# timer_rtc_io.net
KiCad netlist of a schematic drawn in EAGLE
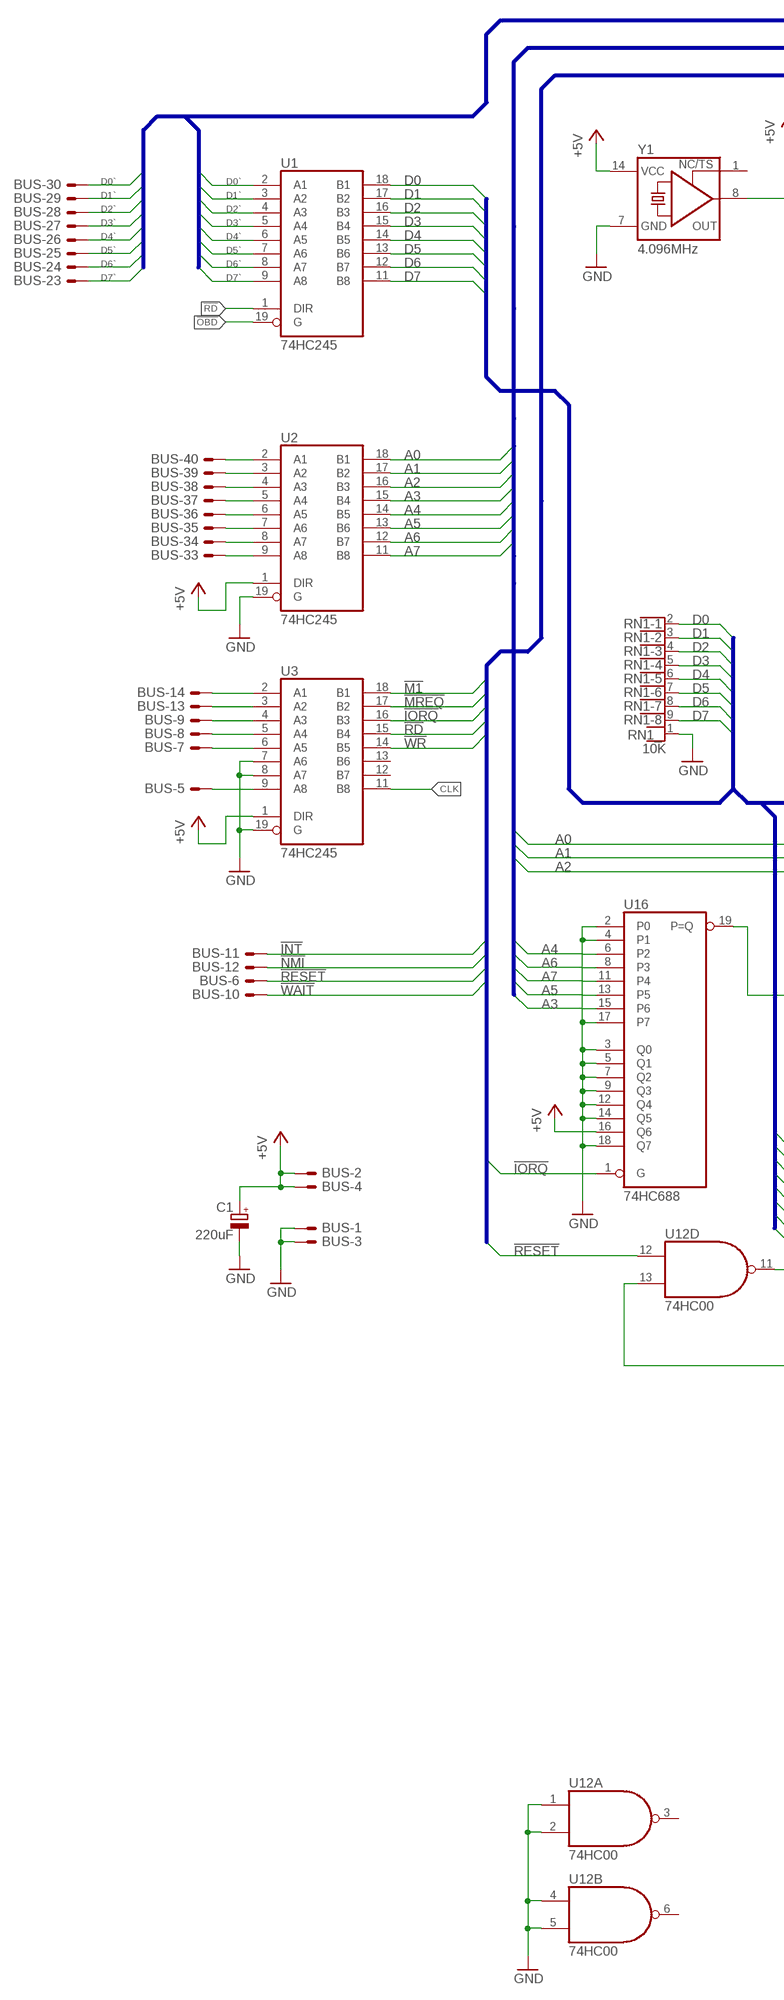
[diagram p0: schematic, sheet 1, part 1 of 2]
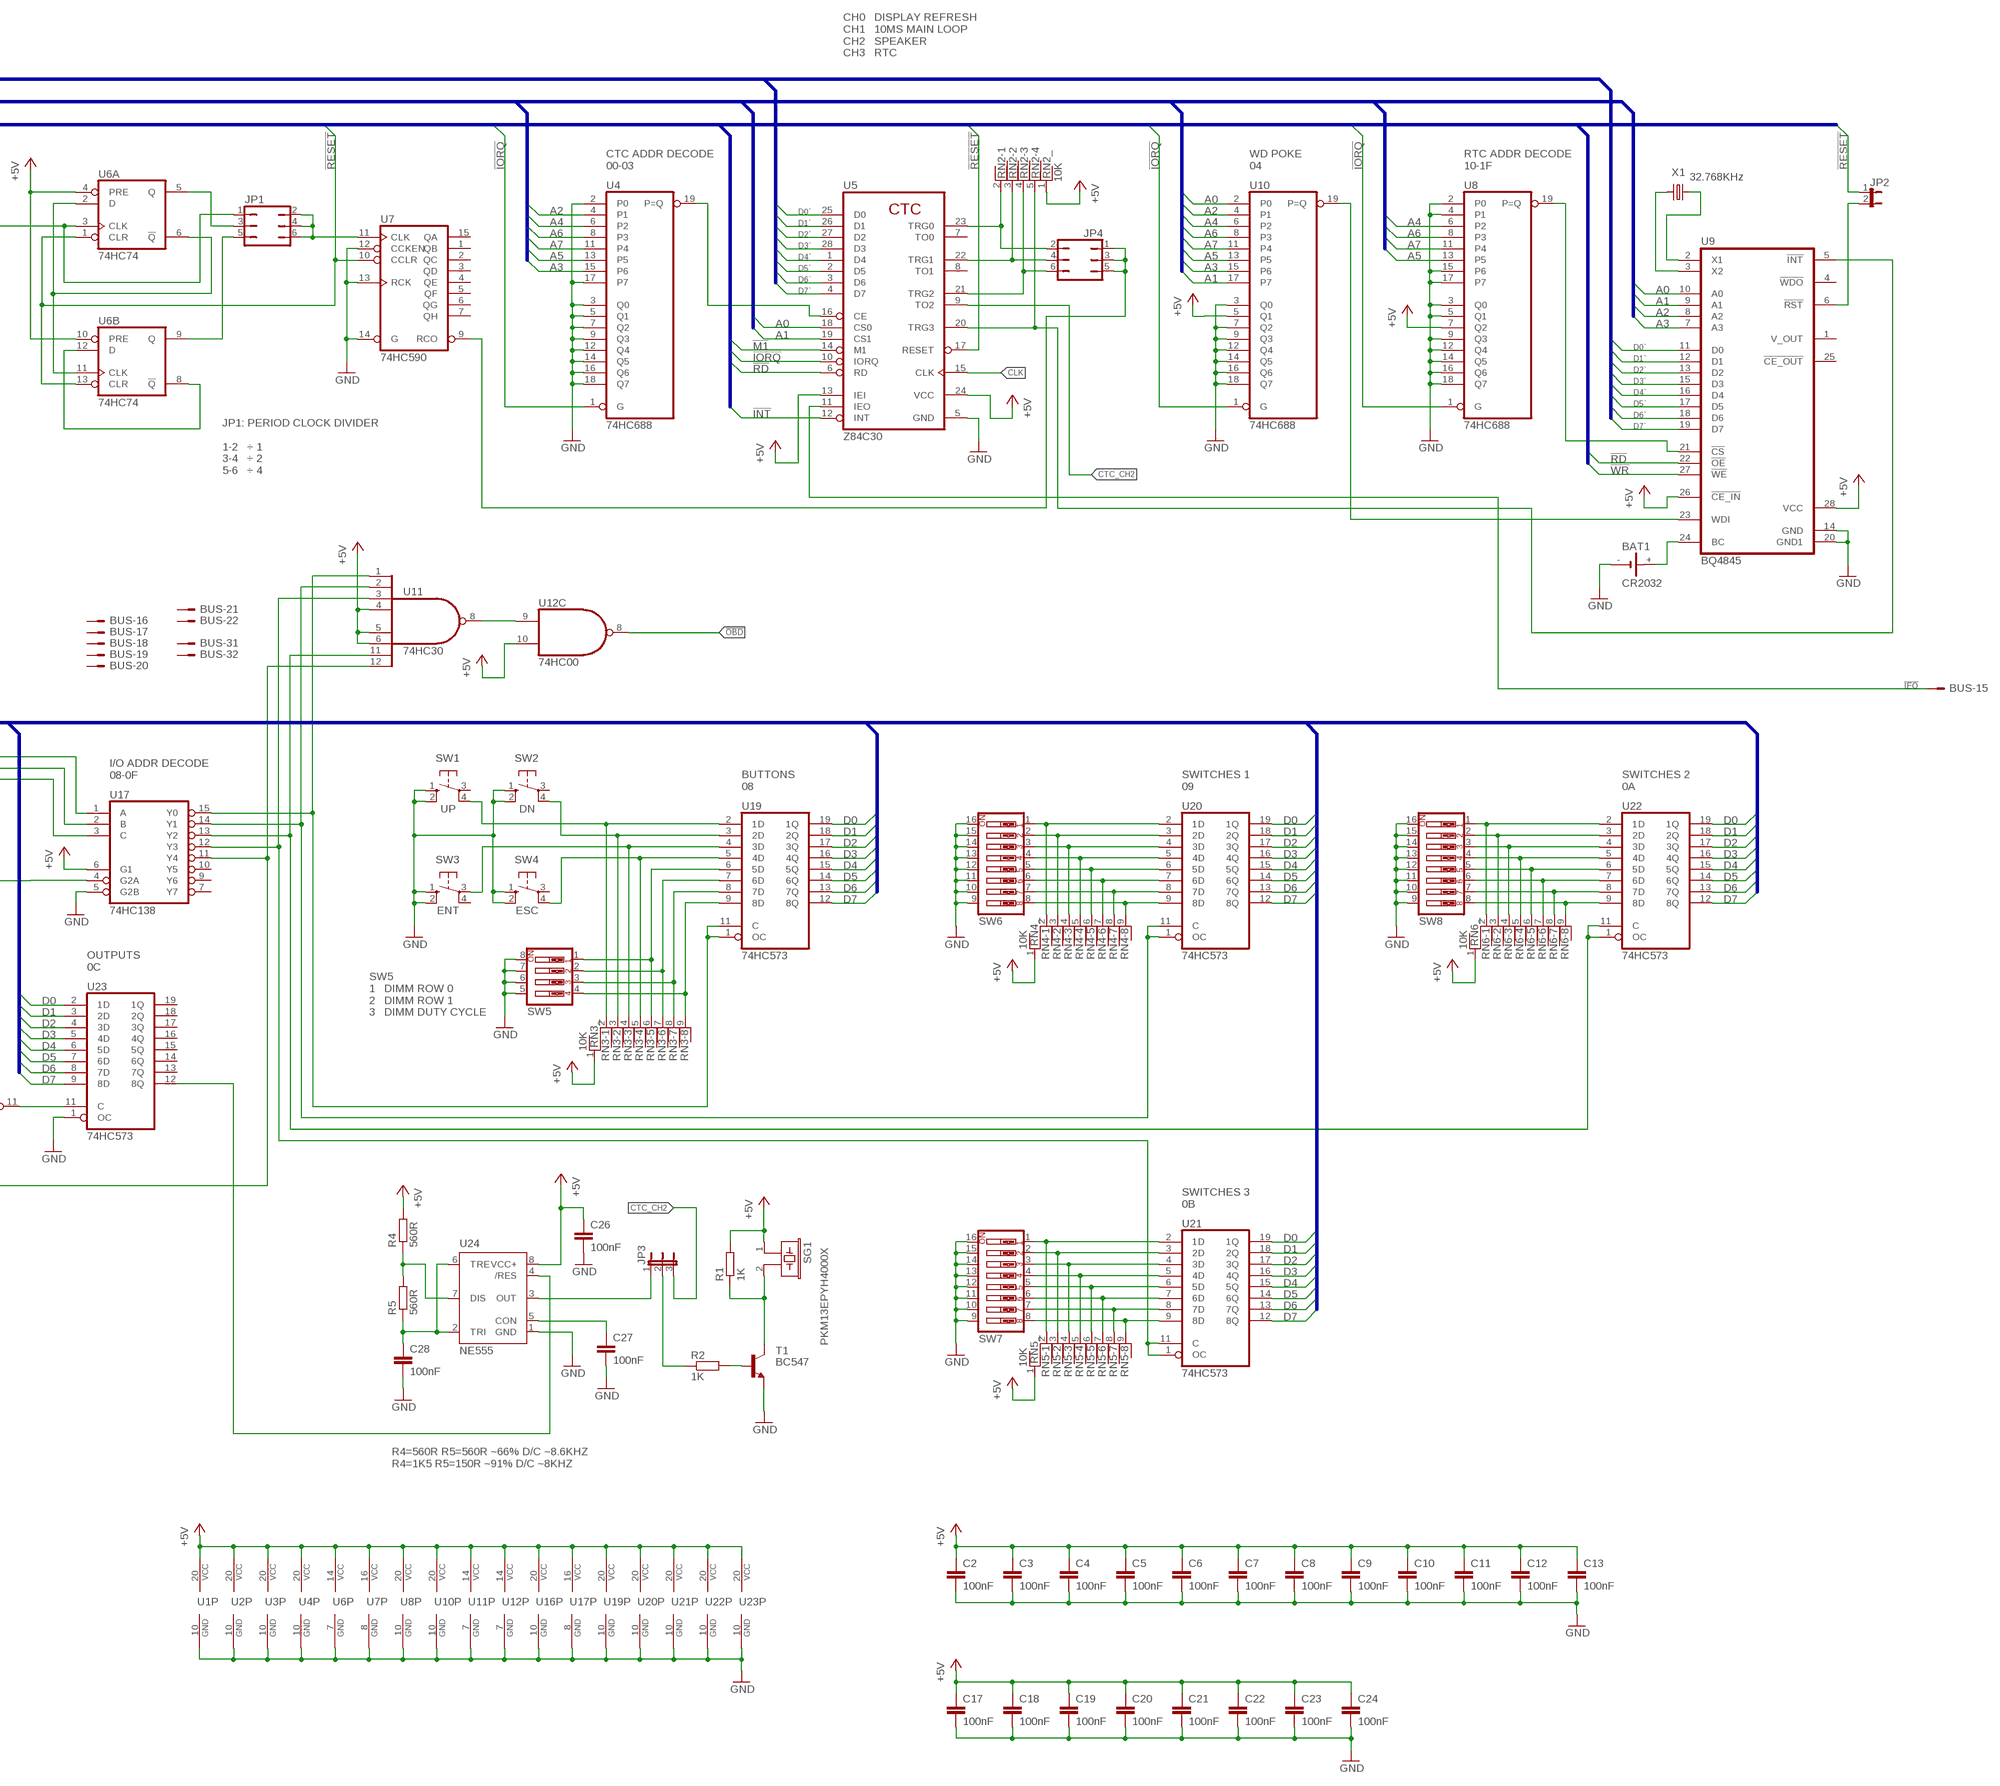
[diagram p1: schematic, sheet 1, part 2 of 2]

(export (version "E")
  (design (tool "Eeschema 10.0.6"))
  (components
    (comp (ref "BAT1")
      (value "CR2032")
      (footprint "eagle-import:CR2032-SMD")
      (libsource (lib "eagle-import") (part "CR2032-SMD"))
    )
    (comp (ref "BUS")
      (value "HDR40")
      (footprint "eagle-import:HDR40")
      (libsource (lib "eagle-import") (part "HDR40"))
    )
    (comp (ref "C1")
      (value "220uF")
      (footprint "eagle-import:E3,5-8")
      (libsource (lib "eagle-import") (part "CPOL-EUE3.5-8"))
    )
    (comp (ref "C2")
      (value "100nF")
      (footprint "eagle-import:C050-025X075")
      (libsource (lib "eagle-import") (part "C-EU050-025X075"))
    )
    (comp (ref "C3")
      (value "100nF")
      (footprint "eagle-import:C050-025X075")
      (libsource (lib "eagle-import") (part "C-EU050-025X075"))
    )
    (comp (ref "C4")
      (value "100nF")
      (footprint "eagle-import:C050-025X075")
      (libsource (lib "eagle-import") (part "C-EU050-025X075"))
    )
    (comp (ref "C5")
      (value "100nF")
      (footprint "eagle-import:C050-025X075")
      (libsource (lib "eagle-import") (part "C-EU050-025X075"))
    )
    (comp (ref "C6")
      (value "100nF")
      (footprint "eagle-import:C050-025X075")
      (libsource (lib "eagle-import") (part "C-EU050-025X075"))
    )
    (comp (ref "C7")
      (value "100nF")
      (footprint "eagle-import:C050-025X075")
      (libsource (lib "eagle-import") (part "C-EU050-025X075"))
    )
    (comp (ref "C8")
      (value "100nF")
      (footprint "eagle-import:C050-025X075")
      (libsource (lib "eagle-import") (part "C-EU050-025X075"))
    )
    (comp (ref "C9")
      (value "100nF")
      (footprint "eagle-import:C050-025X075")
      (libsource (lib "eagle-import") (part "C-EU050-025X075"))
    )
    (comp (ref "C10")
      (value "100nF")
      (footprint "eagle-import:C050-025X075")
      (libsource (lib "eagle-import") (part "C-EU050-025X075"))
    )
    (comp (ref "C11")
      (value "100nF")
      (footprint "eagle-import:C050-025X075")
      (libsource (lib "eagle-import") (part "C-EU050-025X075"))
    )
    (comp (ref "C12")
      (value "100nF")
      (footprint "eagle-import:C050-025X075")
      (libsource (lib "eagle-import") (part "C-EU050-025X075"))
    )
    (comp (ref "C13")
      (value "100nF")
      (footprint "eagle-import:C050-025X075")
      (libsource (lib "eagle-import") (part "C-EU050-025X075"))
    )
    (comp (ref "C17")
      (value "100nF")
      (footprint "eagle-import:C050-025X075")
      (libsource (lib "eagle-import") (part "C-EU050-025X075"))
    )
    (comp (ref "C18")
      (value "100nF")
      (footprint "eagle-import:C050-025X075")
      (libsource (lib "eagle-import") (part "C-EU050-025X075"))
    )
    (comp (ref "C19")
      (value "100nF")
      (footprint "eagle-import:C050-025X075")
      (libsource (lib "eagle-import") (part "C-EU050-025X075"))
    )
    (comp (ref "C20")
      (value "100nF")
      (footprint "eagle-import:C050-025X075")
      (libsource (lib "eagle-import") (part "C-EU050-025X075"))
    )
    (comp (ref "C21")
      (value "100nF")
      (footprint "eagle-import:C050-025X075")
      (libsource (lib "eagle-import") (part "C-EU050-025X075"))
    )
    (comp (ref "C22")
      (value "100nF")
      (footprint "eagle-import:C050-025X075")
      (libsource (lib "eagle-import") (part "C-EU050-025X075"))
    )
    (comp (ref "C23")
      (value "100nF")
      (footprint "eagle-import:C050-025X075")
      (libsource (lib "eagle-import") (part "C-EU050-025X075"))
    )
    (comp (ref "C24")
      (value "100nF")
      (footprint "eagle-import:C050-025X075")
      (libsource (lib "eagle-import") (part "C-EU050-025X075"))
    )
    (comp (ref "C26")
      (value "100nF")
      (footprint "eagle-import:C050-025X075")
      (libsource (lib "eagle-import") (part "C-EU050-025X075"))
    )
    (comp (ref "C27")
      (value "100nF")
      (footprint "eagle-import:C050-025X075")
      (libsource (lib "eagle-import") (part "C-EU050-025X075"))
    )
    (comp (ref "C28")
      (value "100nF")
      (footprint "eagle-import:C050-025X075")
      (libsource (lib "eagle-import") (part "C-EU050-025X075"))
    )
    (comp (ref "JP1")
      (value "JP3Q")
      (footprint "eagle-import:JP3Q")
      (libsource (lib "eagle-import") (part "JP3Q"))
    )
    (comp (ref "JP2")
      (value "JP1E")
      (footprint "eagle-import:JP1")
      (libsource (lib "eagle-import") (part "JP1E"))
    )
    (comp (ref "JP3")
      (value "JP2E")
      (footprint "eagle-import:JP2")
      (libsource (lib "eagle-import") (part "JP2E"))
    )
    (comp (ref "JP4")
      (value "JP3Q")
      (footprint "eagle-import:JP3Q")
      (libsource (lib "eagle-import") (part "JP3Q"))
    )
    (comp (ref "R1")
      (value "1K")
      (footprint "eagle-import:0207_10")
      (libsource (lib "eagle-import") (part "R-EU_0207/10"))
    )
    (comp (ref "R2")
      (value "1K")
      (footprint "eagle-import:0207_10")
      (libsource (lib "eagle-import") (part "R-EU_0207/10"))
    )
    (comp (ref "R4")
      (value "560R")
      (footprint "eagle-import:0207_10")
      (libsource (lib "eagle-import") (part "R-EU_0207/10"))
    )
    (comp (ref "R5")
      (value "560R")
      (footprint "eagle-import:0207_10")
      (libsource (lib "eagle-import") (part "R-EU_0207/10"))
    )
    (comp (ref "RN1")
      (value "10K")
      (footprint "eagle-import:RN-9")
      (libsource (lib "eagle-import") (part "RNX8"))
    )
    (comp (ref "RN2")
      (value "10K")
      (footprint "eagle-import:RN-5")
      (libsource (lib "eagle-import") (part "RNX4"))
    )
    (comp (ref "RN3")
      (value "10K")
      (footprint "eagle-import:RN-9")
      (libsource (lib "eagle-import") (part "RNX8"))
    )
    (comp (ref "RN4")
      (value "10K")
      (footprint "eagle-import:RN-9")
      (libsource (lib "eagle-import") (part "RNX8"))
    )
    (comp (ref "RN5")
      (value "10K")
      (footprint "eagle-import:RN-9")
      (libsource (lib "eagle-import") (part "RNX8"))
    )
    (comp (ref "RN6")
      (value "10K")
      (footprint "eagle-import:RN-9")
      (libsource (lib "eagle-import") (part "RNX8"))
    )
    (comp (ref "SG1")
      (value "PKM13EPYH4000X")
      (footprint "eagle-import:PKM13EPYH400X")
      (libsource (lib "eagle-import") (part "PKM13EPYH4000X"))
    )
    (comp (ref "SW1")
      (value "10-XX")
      (footprint "eagle-import:B3F-10XX")
      (fields (field (name "MPN") "B3F-1000"))
      (libsource (lib "eagle-import") (part "10-XX"))
    )
    (comp (ref "SW2")
      (value "10-XX")
      (footprint "eagle-import:B3F-10XX")
      (fields (field (name "MPN") "B3F-1000"))
      (libsource (lib "eagle-import") (part "10-XX"))
    )
    (comp (ref "SW3")
      (value "10-XX")
      (footprint "eagle-import:B3F-10XX")
      (fields (field (name "MPN") "B3F-1000"))
      (libsource (lib "eagle-import") (part "10-XX"))
    )
    (comp (ref "SW4")
      (value "10-XX")
      (footprint "eagle-import:B3F-10XX")
      (fields (field (name "MPN") "B3F-1000"))
      (libsource (lib "eagle-import") (part "10-XX"))
    )
    (comp (ref "SW5")
      (value "SW_DIP-4")
      (footprint "eagle-import:EDG-04")
      (libsource (lib "eagle-import") (part "SW_DIP-4"))
    )
    (comp (ref "SW6")
      (value "SW_DIP-8")
      (footprint "eagle-import:EDG-08")
      (libsource (lib "eagle-import") (part "SW_DIP-8"))
    )
    (comp (ref "SW7")
      (value "SW_DIP-8")
      (footprint "eagle-import:EDG-08")
      (libsource (lib "eagle-import") (part "SW_DIP-8"))
    )
    (comp (ref "SW8")
      (value "SW_DIP-8")
      (footprint "eagle-import:EDG-08")
      (libsource (lib "eagle-import") (part "SW_DIP-8"))
    )
    (comp (ref "T1")
      (value "BC547")
      (footprint "eagle-import:TO92")
      (libsource (lib "eagle-import") (part "BC547"))
    )
    (comp (ref "U1")
      (value "74HC245")
      (footprint "eagle-import:DIL20")
      (libsource (lib "eagle-import") (part "74245NLS"))
    )
    (comp (ref "U2")
      (value "74HC245")
      (footprint "eagle-import:DIL20")
      (libsource (lib "eagle-import") (part "74245NLS"))
    )
    (comp (ref "U3")
      (value "74HC245")
      (footprint "eagle-import:DIL20")
      (libsource (lib "eagle-import") (part "74245NLS"))
    )
    (comp (ref "U4")
      (value "74HC688")
      (footprint "eagle-import:DIL20")
      (libsource (lib "eagle-import") (part "74688NLS"))
    )
    (comp (ref "U5")
      (value "Z84C30")
      (footprint "eagle-import:DIL28")
      (libsource (lib "eagle-import") (part "Z80CTC"))
    )
    (comp (ref "U6")
      (value "74HC74")
      (footprint "eagle-import:DIL14")
      (libsource (lib "eagle-import") (part "7474NLS"))
    )
    (comp (ref "U7")
      (value "74HC590")
      (footprint "eagle-import:DIL16")
      (libsource (lib "eagle-import") (part "74590NLS"))
    )
    (comp (ref "U8")
      (value "74HC688")
      (footprint "eagle-import:DIL20")
      (libsource (lib "eagle-import") (part "74688NLS"))
    )
    (comp (ref "U9")
      (value "BQ4845")
      (footprint "eagle-import:DIL28-6")
      (libsource (lib "eagle-import") (part "BQ4845P"))
    )
    (comp (ref "U10")
      (value "74HC688")
      (footprint "eagle-import:DIL20")
      (libsource (lib "eagle-import") (part "74688NLS"))
    )
    (comp (ref "U11")
      (value "74HC30")
      (footprint "eagle-import:DIL14")
      (libsource (lib "eagle-import") (part "7430NLS"))
    )
    (comp (ref "U12")
      (value "74HC00")
      (footprint "eagle-import:DIL14")
      (libsource (lib "eagle-import") (part "7400NLS"))
    )
    (comp (ref "U16")
      (value "74HC688")
      (footprint "eagle-import:DIL20")
      (libsource (lib "eagle-import") (part "74688NLS"))
    )
    (comp (ref "U17")
      (value "74HC138")
      (footprint "eagle-import:DIL16")
      (libsource (lib "eagle-import") (part "74138NLS"))
    )
    (comp (ref "U19")
      (value "74HC573")
      (footprint "eagle-import:DIL20")
      (libsource (lib "eagle-import") (part "74573NHC"))
    )
    (comp (ref "U20")
      (value "74HC573")
      (footprint "eagle-import:DIL20")
      (libsource (lib "eagle-import") (part "74573NHC"))
    )
    (comp (ref "U21")
      (value "74HC573")
      (footprint "eagle-import:DIL20")
      (libsource (lib "eagle-import") (part "74573NHC"))
    )
    (comp (ref "U22")
      (value "74HC573")
      (footprint "eagle-import:DIL20")
      (libsource (lib "eagle-import") (part "74573NHC"))
    )
    (comp (ref "U23")
      (value "74HC573")
      (footprint "eagle-import:DIL20")
      (libsource (lib "eagle-import") (part "74573NHC"))
    )
    (comp (ref "U24")
      (value "NE555")
      (footprint "eagle-import:DIL-08")
      (fields (field (name "MF") "Arrow Electronics") (field (name "MPN") "NE555N"))
      (libsource (lib "eagle-import") (part "NE555"))
    )
    (comp (ref "X1")
      (value "32.768KHz")
      (footprint "eagle-import:TC38H")
      (libsource (lib "eagle-import") (part "CRYSTALTC38H"))
    )
    (comp (ref "Y1")
      (value "4.096MHz")
      (footprint "eagle-import:DIL14S")
      (libsource (lib "eagle-import") (part "XO-14"))
    )
  )
  (nets
    (net (code "29") (name "+5V") (class "Default")
      (node (ref "BUS") (pin "2") (pinfunction "S_2") (pintype "passive"))
      (node (ref "BUS") (pin "4") (pinfunction "S_4") (pintype "passive"))
      (node (ref "C1") (pin "+") (pinfunction "+_+") (pintype "passive"))
      (node (ref "C10") (pin "1") (pinfunction "1_1") (pintype "passive"))
      (node (ref "C11") (pin "1") (pinfunction "1_1") (pintype "passive"))
      (node (ref "C12") (pin "1") (pinfunction "1_1") (pintype "passive"))
      (node (ref "C13") (pin "1") (pinfunction "1_1") (pintype "passive"))
      (node (ref "C17") (pin "1") (pinfunction "1_1") (pintype "passive"))
      (node (ref "C18") (pin "1") (pinfunction "1_1") (pintype "passive"))
      (node (ref "C19") (pin "1") (pinfunction "1_1") (pintype "passive"))
      (node (ref "C2") (pin "1") (pinfunction "1_1") (pintype "passive"))
      (node (ref "C20") (pin "1") (pinfunction "1_1") (pintype "passive"))
      (node (ref "C21") (pin "1") (pinfunction "1_1") (pintype "passive"))
      (node (ref "C22") (pin "1") (pinfunction "1_1") (pintype "passive"))
      (node (ref "C23") (pin "1") (pinfunction "1_1") (pintype "passive"))
      (node (ref "C24") (pin "1") (pinfunction "1_1") (pintype "passive"))
      (node (ref "C26") (pin "1") (pinfunction "1_1") (pintype "passive"))
      (node (ref "C3") (pin "1") (pinfunction "1_1") (pintype "passive"))
      (node (ref "C4") (pin "1") (pinfunction "1_1") (pintype "passive"))
      (node (ref "C5") (pin "1") (pinfunction "1_1") (pintype "passive"))
      (node (ref "C6") (pin "1") (pinfunction "1_1") (pintype "passive"))
      (node (ref "C7") (pin "1") (pinfunction "1_1") (pintype "passive"))
      (node (ref "C8") (pin "1") (pinfunction "1_1") (pintype "passive"))
      (node (ref "C9") (pin "1") (pinfunction "1_1") (pintype "passive"))
      (node (ref "R1") (pin "2") (pinfunction "2_2") (pintype "passive"))
      (node (ref "R4") (pin "2") (pinfunction "2_2") (pintype "passive"))
      (node (ref "RN2") (pin "1") (pinfunction "1_1") (pintype "passive"))
      (node (ref "RN3") (pin "1") (pinfunction "1_1") (pintype "passive"))
      (node (ref "RN4") (pin "1") (pinfunction "1_1") (pintype "passive"))
      (node (ref "RN5") (pin "1") (pinfunction "1_1") (pintype "passive"))
      (node (ref "RN6") (pin "1") (pinfunction "1_1") (pintype "passive"))
      (node (ref "SG1") (pin "1") (pinfunction "1_1") (pintype "passive"))
      (node (ref "U1") (pin "20") (pinfunction "VCC_20") (pintype "power_in"))
      (node (ref "U10") (pin "20") (pinfunction "VCC_20") (pintype "power_in"))
      (node (ref "U10") (pin "5") (pinfunction "Q1_5") (pintype "input"))
      (node (ref "U11") (pin "14") (pinfunction "VCC_14") (pintype "power_in"))
      (node (ref "U11") (pin "4") (pinfunction "I3_4") (pintype "input"))
      (node (ref "U11") (pin "5") (pinfunction "I4_5") (pintype "input"))
      (node (ref "U11") (pin "6") (pinfunction "I5_6") (pintype "input"))
      (node (ref "U12") (pin "10") (pinfunction "I1_10") (pintype "input"))
      (node (ref "U12") (pin "14") (pinfunction "VCC_14") (pintype "power_in"))
      (node (ref "U16") (pin "16") (pinfunction "Q6_16") (pintype "input"))
      (node (ref "U16") (pin "20") (pinfunction "VCC_20") (pintype "power_in"))
      (node (ref "U17") (pin "16") (pinfunction "VCC_16") (pintype "power_in"))
      (node (ref "U17") (pin "6") (pinfunction "G1_6") (pintype "input"))
      (node (ref "U19") (pin "20") (pinfunction "VCC_20") (pintype "power_in"))
      (node (ref "U2") (pin "1") (pinfunction "DIR_1") (pintype "input"))
      (node (ref "U2") (pin "20") (pinfunction "VCC_20") (pintype "power_in"))
      (node (ref "U20") (pin "20") (pinfunction "VCC_20") (pintype "power_in"))
      (node (ref "U21") (pin "20") (pinfunction "VCC_20") (pintype "power_in"))
      (node (ref "U22") (pin "20") (pinfunction "VCC_20") (pintype "power_in"))
      (node (ref "U23") (pin "20") (pinfunction "VCC_20") (pintype "power_in"))
      (node (ref "U24") (pin "8") (pinfunction "VCC+_8") (pintype "power_in"))
      (node (ref "U3") (pin "1") (pinfunction "DIR_1") (pintype "input"))
      (node (ref "U3") (pin "20") (pinfunction "VCC_20") (pintype "power_in"))
      (node (ref "U4") (pin "20") (pinfunction "VCC_20") (pintype "power_in"))
      (node (ref "U5") (pin "13") (pinfunction "IEI_13") (pintype "input"))
      (node (ref "U5") (pin "24") (pinfunction "VCC_24") (pintype "power_in"))
      (node (ref "U6") (pin "10") (pinfunction "PRE_10") (pintype "input"))
      (node (ref "U6") (pin "14") (pinfunction "VCC_14") (pintype "power_in"))
      (node (ref "U6") (pin "4") (pinfunction "PRE_4") (pintype "input"))
      (node (ref "U7") (pin "16") (pinfunction "VCC_16") (pintype "power_in"))
      (node (ref "U8") (pin "20") (pinfunction "VCC_20") (pintype "power_in"))
      (node (ref "U8") (pin "7") (pinfunction "Q2_7") (pintype "input"))
      (node (ref "U9") (pin "26") (pinfunction "~{CE_IN}_26") (pintype "input"))
      (node (ref "U9") (pin "28") (pinfunction "VCC_28") (pintype "power_in"))
      (node (ref "Y1") (pin "14") (pinfunction "VCC_14") (pintype "power_in"))
    )
    (net (code "30") (name "/A0") (class "Default")
      (node (ref "U10") (pin "2") (pinfunction "P0_2") (pintype "input"))
      (node (ref "U17") (pin "1") (pinfunction "A_1") (pintype "input"))
      (node (ref "U2") (pin "18") (pinfunction "B1_18") (pintype "bidirectional"))
      (node (ref "U5") (pin "18") (pinfunction "CS0_18") (pintype "input"))
      (node (ref "U9") (pin "10") (pinfunction "A0_10") (pintype "input"))
    )
    (net (code "31") (name "/A1") (class "Default")
      (node (ref "U10") (pin "17") (pinfunction "P7_17") (pintype "input"))
      (node (ref "U17") (pin "2") (pinfunction "B_2") (pintype "input"))
      (node (ref "U2") (pin "17") (pinfunction "B2_17") (pintype "bidirectional"))
      (node (ref "U5") (pin "19") (pinfunction "CS1_19") (pintype "input"))
      (node (ref "U9") (pin "9") (pinfunction "A1_9") (pintype "input"))
    )
    (net (code "32") (name "/A2") (class "Default")
      (node (ref "U10") (pin "4") (pinfunction "P1_4") (pintype "input"))
      (node (ref "U17") (pin "3") (pinfunction "C_3") (pintype "input"))
      (node (ref "U2") (pin "16") (pinfunction "B3_16") (pintype "bidirectional"))
      (node (ref "U4") (pin "4") (pinfunction "P1_4") (pintype "input"))
      (node (ref "U9") (pin "8") (pinfunction "A2_8") (pintype "input"))
    )
    (net (code "33") (name "/A4") (class "Default")
      (node (ref "U10") (pin "6") (pinfunction "P2_6") (pintype "input"))
      (node (ref "U16") (pin "6") (pinfunction "P2_6") (pintype "input"))
      (node (ref "U2") (pin "14") (pinfunction "B5_14") (pintype "bidirectional"))
      (node (ref "U4") (pin "6") (pinfunction "P2_6") (pintype "input"))
      (node (ref "U8") (pin "6") (pinfunction "P2_6") (pintype "input"))
    )
    (net (code "34") (name "/A5") (class "Default")
      (node (ref "U10") (pin "13") (pinfunction "P5_13") (pintype "input"))
      (node (ref "U16") (pin "13") (pinfunction "P5_13") (pintype "input"))
      (node (ref "U2") (pin "13") (pinfunction "B6_13") (pintype "bidirectional"))
      (node (ref "U4") (pin "13") (pinfunction "P5_13") (pintype "input"))
      (node (ref "U8") (pin "13") (pinfunction "P5_13") (pintype "input"))
    )
    (net (code "35") (name "/A6") (class "Default")
      (node (ref "U10") (pin "8") (pinfunction "P3_8") (pintype "input"))
      (node (ref "U16") (pin "8") (pinfunction "P3_8") (pintype "input"))
      (node (ref "U2") (pin "12") (pinfunction "B7_12") (pintype "bidirectional"))
      (node (ref "U4") (pin "8") (pinfunction "P3_8") (pintype "input"))
      (node (ref "U8") (pin "8") (pinfunction "P3_8") (pintype "input"))
    )
    (net (code "36") (name "/A7") (class "Default")
      (node (ref "U10") (pin "11") (pinfunction "P4_11") (pintype "input"))
      (node (ref "U16") (pin "11") (pinfunction "P4_11") (pintype "input"))
      (node (ref "U2") (pin "11") (pinfunction "B8_11") (pintype "bidirectional"))
      (node (ref "U4") (pin "11") (pinfunction "P4_11") (pintype "input"))
      (node (ref "U8") (pin "11") (pinfunction "P4_11") (pintype "input"))
    )
    (net (code "37") (name "/D0") (class "Default")
      (node (ref "RN1") (pin "2") (pinfunction "1_2") (pintype "passive"))
      (node (ref "U1") (pin "18") (pinfunction "B1_18") (pintype "bidirectional"))
      (node (ref "U19") (pin "19") (pinfunction "1Q_19") (pintype "tri_state"))
      (node (ref "U20") (pin "19") (pinfunction "1Q_19") (pintype "tri_state"))
      (node (ref "U21") (pin "19") (pinfunction "1Q_19") (pintype "tri_state"))
      (node (ref "U22") (pin "19") (pinfunction "1Q_19") (pintype "tri_state"))
      (node (ref "U23") (pin "2") (pinfunction "1D_2") (pintype "input"))
    )
    (net (code "38") (name "/D0`") (class "Default")
      (node (ref "BUS") (pin "30") (pinfunction "S_30") (pintype "passive"))
      (node (ref "U1") (pin "2") (pinfunction "A1_2") (pintype "bidirectional"))
      (node (ref "U5") (pin "25") (pinfunction "D0_25") (pintype "bidirectional"))
      (node (ref "U9") (pin "11") (pinfunction "D0_11") (pintype "bidirectional"))
    )
    (net (code "39") (name "/D1") (class "Default")
      (node (ref "RN1") (pin "3") (pinfunction "1_3") (pintype "passive"))
      (node (ref "U1") (pin "17") (pinfunction "B2_17") (pintype "bidirectional"))
      (node (ref "U19") (pin "18") (pinfunction "2Q_18") (pintype "tri_state"))
      (node (ref "U20") (pin "18") (pinfunction "2Q_18") (pintype "tri_state"))
      (node (ref "U21") (pin "18") (pinfunction "2Q_18") (pintype "tri_state"))
      (node (ref "U22") (pin "18") (pinfunction "2Q_18") (pintype "tri_state"))
      (node (ref "U23") (pin "3") (pinfunction "2D_3") (pintype "input"))
    )
    (net (code "40") (name "/D1`") (class "Default")
      (node (ref "BUS") (pin "29") (pinfunction "S_29") (pintype "passive"))
      (node (ref "U1") (pin "3") (pinfunction "A2_3") (pintype "bidirectional"))
      (node (ref "U5") (pin "26") (pinfunction "D1_26") (pintype "bidirectional"))
      (node (ref "U9") (pin "12") (pinfunction "D1_12") (pintype "bidirectional"))
    )
    (net (code "41") (name "/D2") (class "Default")
      (node (ref "RN1") (pin "4") (pinfunction "1_4") (pintype "passive"))
      (node (ref "U1") (pin "16") (pinfunction "B3_16") (pintype "bidirectional"))
      (node (ref "U19") (pin "17") (pinfunction "3Q_17") (pintype "tri_state"))
      (node (ref "U20") (pin "17") (pinfunction "3Q_17") (pintype "tri_state"))
      (node (ref "U21") (pin "17") (pinfunction "3Q_17") (pintype "tri_state"))
      (node (ref "U22") (pin "17") (pinfunction "3Q_17") (pintype "tri_state"))
      (node (ref "U23") (pin "4") (pinfunction "3D_4") (pintype "input"))
    )
    (net (code "42") (name "/D2`") (class "Default")
      (node (ref "BUS") (pin "28") (pinfunction "S_28") (pintype "passive"))
      (node (ref "U1") (pin "4") (pinfunction "A3_4") (pintype "bidirectional"))
      (node (ref "U5") (pin "27") (pinfunction "D2_27") (pintype "bidirectional"))
      (node (ref "U9") (pin "13") (pinfunction "D2_13") (pintype "bidirectional"))
    )
    (net (code "43") (name "/D3") (class "Default")
      (node (ref "RN1") (pin "5") (pinfunction "1_5") (pintype "passive"))
      (node (ref "U1") (pin "15") (pinfunction "B4_15") (pintype "bidirectional"))
      (node (ref "U19") (pin "16") (pinfunction "4Q_16") (pintype "tri_state"))
      (node (ref "U20") (pin "16") (pinfunction "4Q_16") (pintype "tri_state"))
      (node (ref "U21") (pin "16") (pinfunction "4Q_16") (pintype "tri_state"))
      (node (ref "U22") (pin "16") (pinfunction "4Q_16") (pintype "tri_state"))
      (node (ref "U23") (pin "5") (pinfunction "4D_5") (pintype "input"))
    )
    (net (code "44") (name "/D3`") (class "Default")
      (node (ref "BUS") (pin "27") (pinfunction "S_27") (pintype "passive"))
      (node (ref "U1") (pin "5") (pinfunction "A4_5") (pintype "bidirectional"))
      (node (ref "U5") (pin "28") (pinfunction "D3_28") (pintype "bidirectional"))
      (node (ref "U9") (pin "15") (pinfunction "D3_15") (pintype "bidirectional"))
    )
    (net (code "45") (name "/D4") (class "Default")
      (node (ref "RN1") (pin "6") (pinfunction "1_6") (pintype "passive"))
      (node (ref "U1") (pin "14") (pinfunction "B5_14") (pintype "bidirectional"))
      (node (ref "U19") (pin "15") (pinfunction "5Q_15") (pintype "tri_state"))
      (node (ref "U20") (pin "15") (pinfunction "5Q_15") (pintype "tri_state"))
      (node (ref "U21") (pin "15") (pinfunction "5Q_15") (pintype "tri_state"))
      (node (ref "U22") (pin "15") (pinfunction "5Q_15") (pintype "tri_state"))
      (node (ref "U23") (pin "6") (pinfunction "5D_6") (pintype "input"))
    )
    (net (code "46") (name "/D4`") (class "Default")
      (node (ref "BUS") (pin "26") (pinfunction "S_26") (pintype "passive"))
      (node (ref "U1") (pin "6") (pinfunction "A5_6") (pintype "bidirectional"))
      (node (ref "U5") (pin "1") (pinfunction "D4_1") (pintype "bidirectional"))
      (node (ref "U9") (pin "16") (pinfunction "D4_16") (pintype "bidirectional"))
    )
    (net (code "47") (name "/D5") (class "Default")
      (node (ref "RN1") (pin "7") (pinfunction "1_7") (pintype "passive"))
      (node (ref "U1") (pin "13") (pinfunction "B6_13") (pintype "bidirectional"))
      (node (ref "U19") (pin "14") (pinfunction "6Q_14") (pintype "tri_state"))
      (node (ref "U20") (pin "14") (pinfunction "6Q_14") (pintype "tri_state"))
      (node (ref "U21") (pin "14") (pinfunction "6Q_14") (pintype "tri_state"))
      (node (ref "U22") (pin "14") (pinfunction "6Q_14") (pintype "tri_state"))
      (node (ref "U23") (pin "7") (pinfunction "6D_7") (pintype "input"))
    )
    (net (code "48") (name "/D5`") (class "Default")
      (node (ref "BUS") (pin "25") (pinfunction "S_25") (pintype "passive"))
      (node (ref "U1") (pin "7") (pinfunction "A6_7") (pintype "bidirectional"))
      (node (ref "U5") (pin "2") (pinfunction "D5_2") (pintype "bidirectional"))
      (node (ref "U9") (pin "17") (pinfunction "D5_17") (pintype "bidirectional"))
    )
    (net (code "49") (name "/D6") (class "Default")
      (node (ref "RN1") (pin "8") (pinfunction "1_8") (pintype "passive"))
      (node (ref "U1") (pin "12") (pinfunction "B7_12") (pintype "bidirectional"))
      (node (ref "U19") (pin "13") (pinfunction "7Q_13") (pintype "tri_state"))
      (node (ref "U20") (pin "13") (pinfunction "7Q_13") (pintype "tri_state"))
      (node (ref "U21") (pin "13") (pinfunction "7Q_13") (pintype "tri_state"))
      (node (ref "U22") (pin "13") (pinfunction "7Q_13") (pintype "tri_state"))
      (node (ref "U23") (pin "8") (pinfunction "7D_8") (pintype "input"))
    )
    (net (code "50") (name "/D6`") (class "Default")
      (node (ref "BUS") (pin "24") (pinfunction "S_24") (pintype "passive"))
      (node (ref "U1") (pin "8") (pinfunction "A7_8") (pintype "bidirectional"))
      (node (ref "U5") (pin "3") (pinfunction "D6_3") (pintype "bidirectional"))
      (node (ref "U9") (pin "18") (pinfunction "D6_18") (pintype "bidirectional"))
    )
    (net (code "51") (name "/D7") (class "Default")
      (node (ref "RN1") (pin "9") (pinfunction "1_9") (pintype "passive"))
      (node (ref "U1") (pin "11") (pinfunction "B8_11") (pintype "bidirectional"))
      (node (ref "U19") (pin "12") (pinfunction "8Q_12") (pintype "tri_state"))
      (node (ref "U20") (pin "12") (pinfunction "8Q_12") (pintype "tri_state"))
      (node (ref "U21") (pin "12") (pinfunction "8Q_12") (pintype "tri_state"))
      (node (ref "U22") (pin "12") (pinfunction "8Q_12") (pintype "tri_state"))
      (node (ref "U23") (pin "9") (pinfunction "8D_9") (pintype "input"))
    )
    (net (code "52") (name "/D7`") (class "Default")
      (node (ref "BUS") (pin "23") (pinfunction "S_23") (pintype "passive"))
      (node (ref "U1") (pin "9") (pinfunction "A8_9") (pintype "bidirectional"))
      (node (ref "U5") (pin "4") (pinfunction "D7_4") (pintype "bidirectional"))
      (node (ref "U9") (pin "19") (pinfunction "D7_19") (pintype "bidirectional"))
    )
    (net (code "53") (name "/Z80ADDRESS:A0") (class "Default")
      (node (ref "U10") (pin "15") (pinfunction "P6_15") (pintype "input"))
      (node (ref "U16") (pin "15") (pinfunction "P6_15") (pintype "input"))
      (node (ref "U2") (pin "15") (pinfunction "B4_15") (pintype "bidirectional"))
      (node (ref "U4") (pin "15") (pinfunction "P6_15") (pintype "input"))
      (node (ref "U9") (pin "7") (pinfunction "A3_7") (pintype "input"))
    )
    (net (code "57") (name "/~{IEO}") (class "Default")
      (node (ref "BUS") (pin "15") (pinfunction "S_15") (pintype "passive"))
      (node (ref "U5") (pin "11") (pinfunction "IEO_11") (pintype "output"))
    )
    (net (code "58") (name "/~{INT}") (class "Default")
      (node (ref "BUS") (pin "11") (pinfunction "S_11") (pintype "passive"))
      (node (ref "U5") (pin "12") (pinfunction "INT_12") (pintype "output"))
    )
    (net (code "59") (name "/~{IORQ}") (class "Default")
      (node (ref "U10") (pin "1") (pinfunction "G_1") (pintype "input"))
      (node (ref "U16") (pin "1") (pinfunction "G_1") (pintype "input"))
      (node (ref "U3") (pin "16") (pinfunction "B3_16") (pintype "bidirectional"))
      (node (ref "U4") (pin "1") (pinfunction "G_1") (pintype "input"))
      (node (ref "U5") (pin "10") (pinfunction "IORQ_10") (pintype "input"))
      (node (ref "U8") (pin "1") (pinfunction "G_1") (pintype "input"))
    )
    (net (code "60") (name "/~{M1}") (class "Default")
      (node (ref "U3") (pin "18") (pinfunction "B1_18") (pintype "bidirectional"))
      (node (ref "U5") (pin "14") (pinfunction "M1_14") (pintype "input"))
    )
    (net (code "61") (name "/~{MREQ}") (class "Default")
      (node (ref "U3") (pin "17") (pinfunction "B2_17") (pintype "bidirectional"))
    )
    (net (code "62") (name "/~{NMI}") (class "Default")
      (node (ref "BUS") (pin "12") (pinfunction "S_12") (pintype "passive"))
    )
    (net (code "63") (name "/~{OBD}") (class "Default")
      (node (ref "U1") (pin "19") (pinfunction "G_19") (pintype "input"))
      (node (ref "U12") (pin "8") (pinfunction "O_8") (pintype "output"))
    )
    (net (code "64") (name "/~{RD}") (class "Default")
      (node (ref "U1") (pin "1") (pinfunction "DIR_1") (pintype "input"))
      (node (ref "U3") (pin "15") (pinfunction "B4_15") (pintype "bidirectional"))
      (node (ref "U5") (pin "6") (pinfunction "RD_6") (pintype "input"))
      (node (ref "U9") (pin "22") (pinfunction "~{OE}_22") (pintype "input"))
    )
    (net (code "65") (name "/~{RESET}") (class "Default")
      (node (ref "BUS") (pin "6") (pinfunction "S_6") (pintype "passive"))
      (node (ref "JP2") (pin "1") (pinfunction "1_1") (pintype "passive"))
      (node (ref "U12") (pin "12") (pinfunction "I0_12") (pintype "input"))
      (node (ref "U5") (pin "17") (pinfunction "RESET_17") (pintype "input"))
      (node (ref "U6") (pin "1") (pinfunction "CLR_1") (pintype "input"))
      (node (ref "U6") (pin "13") (pinfunction "CLR_13") (pintype "input"))
      (node (ref "U7") (pin "10") (pinfunction "CCLR_10") (pintype "input"))
    )
    (net (code "66") (name "/~{WAIT}") (class "Default")
      (node (ref "BUS") (pin "10") (pinfunction "S_10") (pintype "passive"))
    )
    (net (code "67") (name "/~{WR}") (class "Default")
      (node (ref "U3") (pin "14") (pinfunction "B5_14") (pintype "bidirectional"))
      (node (ref "U9") (pin "27") (pinfunction "~{WE}_27") (pintype "input"))
    )
    (net (code "68") (name "CLK") (class "Default")
      (node (ref "U3") (pin "11") (pinfunction "B8_11") (pintype "bidirectional"))
      (node (ref "U5") (pin "15") (pinfunction "CLK_15") (pintype "input"))
    )
    (net (code "69") (name "CTC_CH2") (class "Default")
      (node (ref "JP3") (pin "3") (pinfunction "3_3") (pintype "passive"))
      (node (ref "U5") (pin "9") (pinfunction "TO2_9") (pintype "output"))
    )
    (net (code "70") (name "GND") (class "Default")
      (node (ref "BAT1") (pin "-") (pinfunction "-_-") (pintype "passive"))
      (node (ref "BUS") (pin "1") (pinfunction "S_1") (pintype "passive"))
      (node (ref "BUS") (pin "3") (pinfunction "S_3") (pintype "passive"))
      (node (ref "C1") (pin "-") (pinfunction "-_-") (pintype "passive"))
      (node (ref "C10") (pin "2") (pinfunction "2_2") (pintype "passive"))
      (node (ref "C11") (pin "2") (pinfunction "2_2") (pintype "passive"))
      (node (ref "C12") (pin "2") (pinfunction "2_2") (pintype "passive"))
      (node (ref "C13") (pin "2") (pinfunction "2_2") (pintype "passive"))
      (node (ref "C17") (pin "2") (pinfunction "2_2") (pintype "passive"))
      (node (ref "C18") (pin "2") (pinfunction "2_2") (pintype "passive"))
      (node (ref "C19") (pin "2") (pinfunction "2_2") (pintype "passive"))
      (node (ref "C2") (pin "2") (pinfunction "2_2") (pintype "passive"))
      (node (ref "C20") (pin "2") (pinfunction "2_2") (pintype "passive"))
      (node (ref "C21") (pin "2") (pinfunction "2_2") (pintype "passive"))
      (node (ref "C22") (pin "2") (pinfunction "2_2") (pintype "passive"))
      (node (ref "C23") (pin "2") (pinfunction "2_2") (pintype "passive"))
      (node (ref "C24") (pin "2") (pinfunction "2_2") (pintype "passive"))
      (node (ref "C26") (pin "2") (pinfunction "2_2") (pintype "passive"))
      (node (ref "C27") (pin "2") (pinfunction "2_2") (pintype "passive"))
      (node (ref "C28") (pin "2") (pinfunction "2_2") (pintype "passive"))
      (node (ref "C3") (pin "2") (pinfunction "2_2") (pintype "passive"))
      (node (ref "C4") (pin "2") (pinfunction "2_2") (pintype "passive"))
      (node (ref "C5") (pin "2") (pinfunction "2_2") (pintype "passive"))
      (node (ref "C6") (pin "2") (pinfunction "2_2") (pintype "passive"))
      (node (ref "C7") (pin "2") (pinfunction "2_2") (pintype "passive"))
      (node (ref "C8") (pin "2") (pinfunction "2_2") (pintype "passive"))
      (node (ref "C9") (pin "2") (pinfunction "2_2") (pintype "passive"))
      (node (ref "RN1") (pin "1") (pinfunction "1_1") (pintype "passive"))
      (node (ref "SW1") (pin "1") (pinfunction "S_1") (pintype "passive"))
      (node (ref "SW1") (pin "2") (pinfunction "S1_2") (pintype "passive"))
      (node (ref "SW2") (pin "1") (pinfunction "S_1") (pintype "passive"))
      (node (ref "SW2") (pin "2") (pinfunction "S1_2") (pintype "passive"))
      (node (ref "SW3") (pin "1") (pinfunction "S_1") (pintype "passive"))
      (node (ref "SW3") (pin "2") (pinfunction "S1_2") (pintype "passive"))
      (node (ref "SW4") (pin "1") (pinfunction "S_1") (pintype "passive"))
      (node (ref "SW4") (pin "2") (pinfunction "S1_2") (pintype "passive"))
      (node (ref "SW5") (pin "5") (pinfunction "5_5") (pintype "passive"))
      (node (ref "SW5") (pin "6") (pinfunction "6_6") (pintype "passive"))
      (node (ref "SW5") (pin "7") (pinfunction "7_7") (pintype "passive"))
      (node (ref "SW5") (pin "8") (pinfunction "8_8") (pintype "passive"))
      (node (ref "SW6") (pin "10") (pinfunction "10_10") (pintype "passive"))
      (node (ref "SW6") (pin "11") (pinfunction "11_11") (pintype "passive"))
      (node (ref "SW6") (pin "12") (pinfunction "12_12") (pintype "passive"))
      (node (ref "SW6") (pin "13") (pinfunction "13_13") (pintype "passive"))
      (node (ref "SW6") (pin "14") (pinfunction "14_14") (pintype "passive"))
      (node (ref "SW6") (pin "15") (pinfunction "15_15") (pintype "passive"))
      (node (ref "SW6") (pin "16") (pinfunction "16_16") (pintype "passive"))
      (node (ref "SW6") (pin "9") (pinfunction "9_9") (pintype "passive"))
      (node (ref "SW7") (pin "10") (pinfunction "10_10") (pintype "passive"))
      (node (ref "SW7") (pin "11") (pinfunction "11_11") (pintype "passive"))
      (node (ref "SW7") (pin "12") (pinfunction "12_12") (pintype "passive"))
      (node (ref "SW7") (pin "13") (pinfunction "13_13") (pintype "passive"))
      (node (ref "SW7") (pin "14") (pinfunction "14_14") (pintype "passive"))
      (node (ref "SW7") (pin "15") (pinfunction "15_15") (pintype "passive"))
      (node (ref "SW7") (pin "16") (pinfunction "16_16") (pintype "passive"))
      (node (ref "SW7") (pin "9") (pinfunction "9_9") (pintype "passive"))
      (node (ref "SW8") (pin "10") (pinfunction "10_10") (pintype "passive"))
      (node (ref "SW8") (pin "11") (pinfunction "11_11") (pintype "passive"))
      (node (ref "SW8") (pin "12") (pinfunction "12_12") (pintype "passive"))
      (node (ref "SW8") (pin "13") (pinfunction "13_13") (pintype "passive"))
      (node (ref "SW8") (pin "14") (pinfunction "14_14") (pintype "passive"))
      (node (ref "SW8") (pin "15") (pinfunction "15_15") (pintype "passive"))
      (node (ref "SW8") (pin "16") (pinfunction "16_16") (pintype "passive"))
      (node (ref "SW8") (pin "9") (pinfunction "9_9") (pintype "passive"))
      (node (ref "T1") (pin "1") (pinfunction "E_1") (pintype "passive"))
      (node (ref "U1") (pin "10") (pinfunction "GND_10") (pintype "power_in"))
      (node (ref "U10") (pin "10") (pinfunction "GND_10") (pintype "power_in"))
      (node (ref "U10") (pin "12") (pinfunction "Q4_12") (pintype "input"))
      (node (ref "U10") (pin "14") (pinfunction "Q5_14") (pintype "input"))
      (node (ref "U10") (pin "16") (pinfunction "Q6_16") (pintype "input"))
      (node (ref "U10") (pin "18") (pinfunction "Q7_18") (pintype "input"))
      (node (ref "U10") (pin "3") (pinfunction "Q0_3") (pintype "input"))
      (node (ref "U10") (pin "7") (pinfunction "Q2_7") (pintype "input"))
      (node (ref "U10") (pin "9") (pinfunction "Q3_9") (pintype "input"))
      (node (ref "U11") (pin "7") (pinfunction "GND_7") (pintype "power_in"))
      (node (ref "U12") (pin "1") (pinfunction "I0_1") (pintype "input"))
      (node (ref "U12") (pin "2") (pinfunction "I1_2") (pintype "input"))
      (node (ref "U12") (pin "4") (pinfunction "I0_4") (pintype "input"))
      (node (ref "U12") (pin "5") (pinfunction "I1_5") (pintype "input"))
      (node (ref "U12") (pin "7") (pinfunction "GND_7") (pintype "power_in"))
      (node (ref "U16") (pin "10") (pinfunction "GND_10") (pintype "power_in"))
      (node (ref "U16") (pin "12") (pinfunction "Q4_12") (pintype "input"))
      (node (ref "U16") (pin "14") (pinfunction "Q5_14") (pintype "input"))
      (node (ref "U16") (pin "17") (pinfunction "P7_17") (pintype "input"))
      (node (ref "U16") (pin "18") (pinfunction "Q7_18") (pintype "input"))
      (node (ref "U16") (pin "2") (pinfunction "P0_2") (pintype "input"))
      (node (ref "U16") (pin "3") (pinfunction "Q0_3") (pintype "input"))
      (node (ref "U16") (pin "4") (pinfunction "P1_4") (pintype "input"))
      (node (ref "U16") (pin "5") (pinfunction "Q1_5") (pintype "input"))
      (node (ref "U16") (pin "7") (pinfunction "Q2_7") (pintype "input"))
      (node (ref "U16") (pin "9") (pinfunction "Q3_9") (pintype "input"))
      (node (ref "U17") (pin "5") (pinfunction "G2B_5") (pintype "input"))
      (node (ref "U17") (pin "8") (pinfunction "GND_8") (pintype "power_in"))
      (node (ref "U19") (pin "10") (pinfunction "GND_10") (pintype "power_in"))
      (node (ref "U2") (pin "10") (pinfunction "GND_10") (pintype "power_in"))
      (node (ref "U2") (pin "19") (pinfunction "G_19") (pintype "input"))
      (node (ref "U20") (pin "10") (pinfunction "GND_10") (pintype "power_in"))
      (node (ref "U21") (pin "10") (pinfunction "GND_10") (pintype "power_in"))
      (node (ref "U22") (pin "10") (pinfunction "GND_10") (pintype "power_in"))
      (node (ref "U23") (pin "1") (pinfunction "OC_1") (pintype "input"))
      (node (ref "U23") (pin "10") (pinfunction "GND_10") (pintype "power_in"))
      (node (ref "U24") (pin "1") (pinfunction "GND_1") (pintype "power_in"))
      (node (ref "U3") (pin "10") (pinfunction "GND_10") (pintype "power_in"))
      (node (ref "U3") (pin "19") (pinfunction "G_19") (pintype "input"))
      (node (ref "U3") (pin "7") (pinfunction "A6_7") (pintype "bidirectional"))
      (node (ref "U3") (pin "8") (pinfunction "A7_8") (pintype "bidirectional"))
      (node (ref "U4") (pin "10") (pinfunction "GND_10") (pintype "power_in"))
      (node (ref "U4") (pin "12") (pinfunction "Q4_12") (pintype "input"))
      (node (ref "U4") (pin "14") (pinfunction "Q5_14") (pintype "input"))
      (node (ref "U4") (pin "16") (pinfunction "Q6_16") (pintype "input"))
      (node (ref "U4") (pin "17") (pinfunction "P7_17") (pintype "input"))
      (node (ref "U4") (pin "18") (pinfunction "Q7_18") (pintype "input"))
      (node (ref "U4") (pin "2") (pinfunction "P0_2") (pintype "input"))
      (node (ref "U4") (pin "3") (pinfunction "Q0_3") (pintype "input"))
      (node (ref "U4") (pin "5") (pinfunction "Q1_5") (pintype "input"))
      (node (ref "U4") (pin "7") (pinfunction "Q2_7") (pintype "input"))
      (node (ref "U4") (pin "9") (pinfunction "Q3_9") (pintype "input"))
      (node (ref "U5") (pin "5") (pinfunction "GND_5") (pintype "power_in"))
      (node (ref "U6") (pin "7") (pinfunction "GND_7") (pintype "power_in"))
      (node (ref "U7") (pin "12") (pinfunction "CCKEN_12") (pintype "input"))
      (node (ref "U7") (pin "13") (pinfunction "RCK_13") (pintype "input"))
      (node (ref "U7") (pin "14") (pinfunction "G_14") (pintype "input"))
      (node (ref "U7") (pin "8") (pinfunction "GND_8") (pintype "power_in"))
      (node (ref "U8") (pin "10") (pinfunction "GND_10") (pintype "power_in"))
      (node (ref "U8") (pin "12") (pinfunction "Q4_12") (pintype "input"))
      (node (ref "U8") (pin "14") (pinfunction "Q5_14") (pintype "input"))
      (node (ref "U8") (pin "15") (pinfunction "P6_15") (pintype "input"))
      (node (ref "U8") (pin "16") (pinfunction "Q6_16") (pintype "input"))
      (node (ref "U8") (pin "17") (pinfunction "P7_17") (pintype "input"))
      (node (ref "U8") (pin "18") (pinfunction "Q7_18") (pintype "input"))
      (node (ref "U8") (pin "2") (pinfunction "P0_2") (pintype "input"))
      (node (ref "U8") (pin "3") (pinfunction "Q0_3") (pintype "input"))
      (node (ref "U8") (pin "4") (pinfunction "P1_4") (pintype "input"))
      (node (ref "U8") (pin "5") (pinfunction "Q1_5") (pintype "input"))
      (node (ref "U8") (pin "9") (pinfunction "Q3_9") (pintype "input"))
      (node (ref "U9") (pin "14") (pinfunction "GND_14") (pintype "power_in"))
      (node (ref "U9") (pin "20") (pinfunction "GND1_20") (pintype "power_in"))
      (node (ref "Y1") (pin "7") (pinfunction "GND_7") (pintype "power_in"))
    )
    (net (code "71") (name "Net-(BUSAA-S)") (class "Default")
      (node (ref "BUS") (pin "33") (pinfunction "S_33") (pintype "passive"))
      (node (ref "U2") (pin "9") (pinfunction "A8_9") (pintype "bidirectional"))
    )
    (net (code "72") (name "Net-(BUSAB-S)") (class "Default")
      (node (ref "BUS") (pin "34") (pinfunction "S_34") (pintype "passive"))
      (node (ref "U2") (pin "8") (pinfunction "A7_8") (pintype "bidirectional"))
    )
    (net (code "73") (name "Net-(BUSAC-S)") (class "Default")
      (node (ref "BUS") (pin "35") (pinfunction "S_35") (pintype "passive"))
      (node (ref "U2") (pin "7") (pinfunction "A6_7") (pintype "bidirectional"))
    )
    (net (code "74") (name "Net-(BUSAD-S)") (class "Default")
      (node (ref "BUS") (pin "36") (pinfunction "S_36") (pintype "passive"))
      (node (ref "U2") (pin "6") (pinfunction "A5_6") (pintype "bidirectional"))
    )
    (net (code "75") (name "Net-(BUSAE-S)") (class "Default")
      (node (ref "BUS") (pin "37") (pinfunction "S_37") (pintype "passive"))
      (node (ref "U2") (pin "5") (pinfunction "A4_5") (pintype "bidirectional"))
    )
    (net (code "76") (name "Net-(BUSAF-S)") (class "Default")
      (node (ref "BUS") (pin "38") (pinfunction "S_38") (pintype "passive"))
      (node (ref "U2") (pin "4") (pinfunction "A3_4") (pintype "bidirectional"))
    )
    (net (code "77") (name "Net-(BUSAG-S)") (class "Default")
      (node (ref "BUS") (pin "39") (pinfunction "S_39") (pintype "passive"))
      (node (ref "U2") (pin "3") (pinfunction "A2_3") (pintype "bidirectional"))
    )
    (net (code "78") (name "Net-(BUSAI-S)") (class "Default")
      (node (ref "BUS") (pin "40") (pinfunction "S_40") (pintype "passive"))
      (node (ref "U2") (pin "2") (pinfunction "A1_2") (pintype "bidirectional"))
    )
    (net (code "79") (name "Net-(BUSAJ-S)") (class "Default")
      (node (ref "BUS") (pin "5") (pinfunction "S_5") (pintype "passive"))
      (node (ref "U3") (pin "9") (pinfunction "A8_9") (pintype "bidirectional"))
    )
    (net (code "80") (name "Net-(BUSAL-S)") (class "Default")
      (node (ref "BUS") (pin "7") (pinfunction "S_7") (pintype "passive"))
      (node (ref "U3") (pin "6") (pinfunction "A5_6") (pintype "bidirectional"))
    )
    (net (code "81") (name "Net-(BUSAM-S)") (class "Default")
      (node (ref "BUS") (pin "8") (pinfunction "S_8") (pintype "passive"))
      (node (ref "U3") (pin "5") (pinfunction "A4_5") (pintype "bidirectional"))
    )
    (net (code "82") (name "Net-(BUSAN-S)") (class "Default")
      (node (ref "BUS") (pin "9") (pinfunction "S_9") (pintype "passive"))
      (node (ref "U3") (pin "4") (pinfunction "A3_4") (pintype "bidirectional"))
    )
    (net (code "83") (name "Net-(BUSE-S)") (class "Default")
      (node (ref "BUS") (pin "13") (pinfunction "S_13") (pintype "passive"))
      (node (ref "U3") (pin "3") (pinfunction "A2_3") (pintype "bidirectional"))
    )
    (net (code "84") (name "Net-(BUSF-S)") (class "Default")
      (node (ref "BUS") (pin "14") (pinfunction "S_14") (pintype "passive"))
      (node (ref "U3") (pin "2") (pinfunction "A1_2") (pintype "bidirectional"))
    )
    (net (code "85") (name "Net-(JP3-Pad2)") (class "Default")
      (node (ref "JP3") (pin "2") (pinfunction "2_2") (pintype "passive"))
      (node (ref "R2") (pin "1") (pinfunction "1_1") (pintype "passive"))
    )
    (net (code "86") (name "Net-(RN2A-1)") (class "Default")
      (node (ref "JP4") (pin "2") (pinfunction "2_2") (pintype "passive"))
      (node (ref "RN2") (pin "2") (pinfunction "1_2") (pintype "passive"))
      (node (ref "U5") (pin "23") (pinfunction "TRG0_23") (pintype "input"))
    )
    (net (code "87") (name "Net-(RN2B-1)") (class "Default")
      (node (ref "JP4") (pin "4") (pinfunction "4_4") (pintype "passive"))
      (node (ref "RN2") (pin "3") (pinfunction "1_3") (pintype "passive"))
      (node (ref "U5") (pin "22") (pinfunction "TRG1_22") (pintype "input"))
    )
    (net (code "88") (name "Net-(RN2C-1)") (class "Default")
      (node (ref "JP4") (pin "6") (pinfunction "6_6") (pintype "passive"))
      (node (ref "RN2") (pin "4") (pinfunction "1_4") (pintype "passive"))
      (node (ref "U5") (pin "21") (pinfunction "TRG2_21") (pintype "input"))
    )
    (net (code "89") (name "Net-(RN2D-1)") (class "Default")
      (node (ref "RN2") (pin "5") (pinfunction "1_5") (pintype "passive"))
      (node (ref "U5") (pin "20") (pinfunction "TRG3_20") (pintype "input"))
      (node (ref "U9") (pin "5") (pinfunction "~{INT}_5") (pintype "open_collector"))
    )
    (net (code "90") (name "Net-(RN3A-1)") (class "Default")
      (node (ref "RN3") (pin "2") (pinfunction "1_2") (pintype "passive"))
      (node (ref "SW1") (pin "4") (pinfunction "P1_4") (pintype "passive"))
      (node (ref "U19") (pin "2") (pinfunction "1D_2") (pintype "input"))
    )
    (net (code "91") (name "Net-(RN3B-1)") (class "Default")
      (node (ref "RN3") (pin "3") (pinfunction "1_3") (pintype "passive"))
      (node (ref "SW2") (pin "4") (pinfunction "P1_4") (pintype "passive"))
      (node (ref "U19") (pin "3") (pinfunction "2D_3") (pintype "input"))
    )
    (net (code "92") (name "Net-(RN3C-1)") (class "Default")
      (node (ref "RN3") (pin "4") (pinfunction "1_4") (pintype "passive"))
      (node (ref "SW3") (pin "3") (pinfunction "P_3") (pintype "passive"))
      (node (ref "U19") (pin "4") (pinfunction "3D_4") (pintype "input"))
    )
    (net (code "93") (name "Net-(RN3D-1)") (class "Default")
      (node (ref "RN3") (pin "5") (pinfunction "1_5") (pintype "passive"))
      (node (ref "SW4") (pin "4") (pinfunction "P1_4") (pintype "passive"))
      (node (ref "U19") (pin "5") (pinfunction "4D_5") (pintype "input"))
    )
    (net (code "94") (name "Net-(RN3E-1)") (class "Default")
      (node (ref "RN3") (pin "6") (pinfunction "1_6") (pintype "passive"))
      (node (ref "SW5") (pin "1") (pinfunction "1_1") (pintype "passive"))
      (node (ref "U19") (pin "6") (pinfunction "5D_6") (pintype "input"))
    )
    (net (code "95") (name "Net-(RN3F-1)") (class "Default")
      (node (ref "RN3") (pin "7") (pinfunction "1_7") (pintype "passive"))
      (node (ref "SW5") (pin "2") (pinfunction "2_2") (pintype "passive"))
      (node (ref "U19") (pin "7") (pinfunction "6D_7") (pintype "input"))
    )
    (net (code "96") (name "Net-(RN3G-1)") (class "Default")
      (node (ref "RN3") (pin "8") (pinfunction "1_8") (pintype "passive"))
      (node (ref "SW5") (pin "3") (pinfunction "3_3") (pintype "passive"))
      (node (ref "U19") (pin "8") (pinfunction "7D_8") (pintype "input"))
    )
    (net (code "97") (name "Net-(RN3H-1)") (class "Default")
      (node (ref "RN3") (pin "9") (pinfunction "1_9") (pintype "passive"))
      (node (ref "SW5") (pin "4") (pinfunction "4_4") (pintype "passive"))
      (node (ref "U19") (pin "9") (pinfunction "8D_9") (pintype "input"))
    )
    (net (code "98") (name "Net-(RN4A-1)") (class "Default")
      (node (ref "RN4") (pin "2") (pinfunction "1_2") (pintype "passive"))
      (node (ref "SW6") (pin "1") (pinfunction "1_1") (pintype "passive"))
      (node (ref "U20") (pin "2") (pinfunction "1D_2") (pintype "input"))
    )
    (net (code "99") (name "Net-(RN4B-1)") (class "Default")
      (node (ref "RN4") (pin "3") (pinfunction "1_3") (pintype "passive"))
      (node (ref "SW6") (pin "2") (pinfunction "2_2") (pintype "passive"))
      (node (ref "U20") (pin "3") (pinfunction "2D_3") (pintype "input"))
    )
    (net (code "100") (name "Net-(RN4C-1)") (class "Default")
      (node (ref "RN4") (pin "4") (pinfunction "1_4") (pintype "passive"))
      (node (ref "SW6") (pin "3") (pinfunction "3_3") (pintype "passive"))
      (node (ref "U20") (pin "4") (pinfunction "3D_4") (pintype "input"))
    )
    (net (code "101") (name "Net-(RN4D-1)") (class "Default")
      (node (ref "RN4") (pin "5") (pinfunction "1_5") (pintype "passive"))
      (node (ref "SW6") (pin "4") (pinfunction "4_4") (pintype "passive"))
      (node (ref "U20") (pin "5") (pinfunction "4D_5") (pintype "input"))
    )
    (net (code "102") (name "Net-(RN4E-1)") (class "Default")
      (node (ref "RN4") (pin "6") (pinfunction "1_6") (pintype "passive"))
      (node (ref "SW6") (pin "5") (pinfunction "5_5") (pintype "passive"))
      (node (ref "U20") (pin "6") (pinfunction "5D_6") (pintype "input"))
    )
    (net (code "103") (name "Net-(RN4F-1)") (class "Default")
      (node (ref "RN4") (pin "7") (pinfunction "1_7") (pintype "passive"))
      (node (ref "SW6") (pin "6") (pinfunction "6_6") (pintype "passive"))
      (node (ref "U20") (pin "7") (pinfunction "6D_7") (pintype "input"))
    )
    (net (code "104") (name "Net-(RN4G-1)") (class "Default")
      (node (ref "RN4") (pin "8") (pinfunction "1_8") (pintype "passive"))
      (node (ref "SW6") (pin "7") (pinfunction "7_7") (pintype "passive"))
      (node (ref "U20") (pin "8") (pinfunction "7D_8") (pintype "input"))
    )
    (net (code "105") (name "Net-(RN4H-1)") (class "Default")
      (node (ref "RN4") (pin "9") (pinfunction "1_9") (pintype "passive"))
      (node (ref "SW6") (pin "8") (pinfunction "8_8") (pintype "passive"))
      (node (ref "U20") (pin "9") (pinfunction "8D_9") (pintype "input"))
    )
    (net (code "106") (name "Net-(RN5A-1)") (class "Default")
      (node (ref "RN5") (pin "2") (pinfunction "1_2") (pintype "passive"))
      (node (ref "SW7") (pin "1") (pinfunction "1_1") (pintype "passive"))
      (node (ref "U21") (pin "2") (pinfunction "1D_2") (pintype "input"))
    )
    (net (code "107") (name "Net-(RN5B-1)") (class "Default")
      (node (ref "RN5") (pin "3") (pinfunction "1_3") (pintype "passive"))
      (node (ref "SW7") (pin "2") (pinfunction "2_2") (pintype "passive"))
      (node (ref "U21") (pin "3") (pinfunction "2D_3") (pintype "input"))
    )
    (net (code "108") (name "Net-(RN5C-1)") (class "Default")
      (node (ref "RN5") (pin "4") (pinfunction "1_4") (pintype "passive"))
      (node (ref "SW7") (pin "3") (pinfunction "3_3") (pintype "passive"))
      (node (ref "U21") (pin "4") (pinfunction "3D_4") (pintype "input"))
    )
    (net (code "109") (name "Net-(RN5D-1)") (class "Default")
      (node (ref "RN5") (pin "5") (pinfunction "1_5") (pintype "passive"))
      (node (ref "SW7") (pin "4") (pinfunction "4_4") (pintype "passive"))
      (node (ref "U21") (pin "5") (pinfunction "4D_5") (pintype "input"))
    )
    (net (code "110") (name "Net-(RN5E-1)") (class "Default")
      (node (ref "RN5") (pin "6") (pinfunction "1_6") (pintype "passive"))
      (node (ref "SW7") (pin "5") (pinfunction "5_5") (pintype "passive"))
      (node (ref "U21") (pin "6") (pinfunction "5D_6") (pintype "input"))
    )
    (net (code "111") (name "Net-(RN5F-1)") (class "Default")
      (node (ref "RN5") (pin "7") (pinfunction "1_7") (pintype "passive"))
      (node (ref "SW7") (pin "6") (pinfunction "6_6") (pintype "passive"))
      (node (ref "U21") (pin "7") (pinfunction "6D_7") (pintype "input"))
    )
    (net (code "112") (name "Net-(RN5G-1)") (class "Default")
      (node (ref "RN5") (pin "8") (pinfunction "1_8") (pintype "passive"))
      (node (ref "SW7") (pin "7") (pinfunction "7_7") (pintype "passive"))
      (node (ref "U21") (pin "8") (pinfunction "7D_8") (pintype "input"))
    )
    (net (code "113") (name "Net-(RN5H-1)") (class "Default")
      (node (ref "RN5") (pin "9") (pinfunction "1_9") (pintype "passive"))
      (node (ref "SW7") (pin "8") (pinfunction "8_8") (pintype "passive"))
      (node (ref "U21") (pin "9") (pinfunction "8D_9") (pintype "input"))
    )
    (net (code "114") (name "Net-(RN6A-1)") (class "Default")
      (node (ref "RN6") (pin "2") (pinfunction "1_2") (pintype "passive"))
      (node (ref "SW8") (pin "1") (pinfunction "1_1") (pintype "passive"))
      (node (ref "U22") (pin "2") (pinfunction "1D_2") (pintype "input"))
    )
    (net (code "115") (name "Net-(RN6B-1)") (class "Default")
      (node (ref "RN6") (pin "3") (pinfunction "1_3") (pintype "passive"))
      (node (ref "SW8") (pin "2") (pinfunction "2_2") (pintype "passive"))
      (node (ref "U22") (pin "3") (pinfunction "2D_3") (pintype "input"))
    )
    (net (code "116") (name "Net-(RN6C-1)") (class "Default")
      (node (ref "RN6") (pin "4") (pinfunction "1_4") (pintype "passive"))
      (node (ref "SW8") (pin "3") (pinfunction "3_3") (pintype "passive"))
      (node (ref "U22") (pin "4") (pinfunction "3D_4") (pintype "input"))
    )
    (net (code "117") (name "Net-(RN6D-1)") (class "Default")
      (node (ref "RN6") (pin "5") (pinfunction "1_5") (pintype "passive"))
      (node (ref "SW8") (pin "4") (pinfunction "4_4") (pintype "passive"))
      (node (ref "U22") (pin "5") (pinfunction "4D_5") (pintype "input"))
    )
    (net (code "118") (name "Net-(RN6E-1)") (class "Default")
      (node (ref "RN6") (pin "6") (pinfunction "1_6") (pintype "passive"))
      (node (ref "SW8") (pin "5") (pinfunction "5_5") (pintype "passive"))
      (node (ref "U22") (pin "6") (pinfunction "5D_6") (pintype "input"))
    )
    (net (code "119") (name "Net-(RN6F-1)") (class "Default")
      (node (ref "RN6") (pin "7") (pinfunction "1_7") (pintype "passive"))
      (node (ref "SW8") (pin "6") (pinfunction "6_6") (pintype "passive"))
      (node (ref "U22") (pin "7") (pinfunction "6D_7") (pintype "input"))
    )
    (net (code "120") (name "Net-(RN6G-1)") (class "Default")
      (node (ref "RN6") (pin "8") (pinfunction "1_8") (pintype "passive"))
      (node (ref "SW8") (pin "7") (pinfunction "7_7") (pintype "passive"))
      (node (ref "U22") (pin "8") (pinfunction "7D_8") (pintype "input"))
    )
    (net (code "121") (name "Net-(RN6H-1)") (class "Default")
      (node (ref "RN6") (pin "9") (pinfunction "1_9") (pintype "passive"))
      (node (ref "SW8") (pin "8") (pinfunction "8_8") (pintype "passive"))
      (node (ref "U22") (pin "9") (pinfunction "8D_9") (pintype "input"))
    )
    (net (code "122") (name "Net-(T1-B)") (class "Default")
      (node (ref "R2") (pin "2") (pinfunction "2_2") (pintype "passive"))
      (node (ref "T1") (pin "2") (pinfunction "B_2") (pintype "passive"))
    )
    (net (code "123") (name "Net-(T1-C)") (class "Default")
      (node (ref "R1") (pin "1") (pinfunction "1_1") (pintype "passive"))
      (node (ref "SG1") (pin "2") (pinfunction "2_2") (pintype "passive"))
      (node (ref "T1") (pin "3") (pinfunction "C_3") (pintype "passive"))
    )
    (net (code "124") (name "Net-(U4A-P=Q)") (class "Default")
      (node (ref "U4") (pin "19") (pinfunction "P=Q_19") (pintype "output"))
      (node (ref "U5") (pin "16") (pinfunction "CE_16") (pintype "input"))
    )
    (net (code "125") (name "Net-(U6A-CLK)") (class "Default")
      (node (ref "JP1") (pin "1") (pinfunction "1_1") (pintype "passive"))
      (node (ref "U6") (pin "3") (pinfunction "CLK_3") (pintype "input"))
      (node (ref "Y1") (pin "8") (pinfunction "OUT_8") (pintype "output"))
    )
    (net (code "126") (name "Net-(U6A-D)") (class "Default")
      (node (ref "U6") (pin "11") (pinfunction "CLK_11") (pintype "input"))
      (node (ref "U6") (pin "2") (pinfunction "D_2") (pintype "input"))
      (node (ref "U6") (pin "6") (pinfunction "~{Q}_6") (pintype "output"))
    )
    (net (code "127") (name "Net-(U6A-Q)") (class "Default")
      (node (ref "JP1") (pin "3") (pinfunction "3_3") (pintype "passive"))
      (node (ref "U6") (pin "5") (pinfunction "Q_5") (pintype "output"))
    )
    (net (code "128") (name "Net-(U6B-D)") (class "Default")
      (node (ref "U6") (pin "12") (pinfunction "D_12") (pintype "input"))
      (node (ref "U6") (pin "8") (pinfunction "~{Q}_8") (pintype "output"))
    )
    (net (code "129") (name "Net-(U6B-Q)") (class "Default")
      (node (ref "JP1") (pin "5") (pinfunction "5_5") (pintype "passive"))
      (node (ref "U6") (pin "9") (pinfunction "Q_9") (pintype "output"))
    )
    (net (code "130") (name "Net-(U7A-CLK)") (class "Default")
      (node (ref "JP1") (pin "2") (pinfunction "2_2") (pintype "passive"))
      (node (ref "JP1") (pin "4") (pinfunction "4_4") (pintype "passive"))
      (node (ref "JP1") (pin "6") (pinfunction "6_6") (pintype "passive"))
      (node (ref "U7") (pin "11") (pinfunction "CLK_11") (pintype "input"))
    )
    (net (code "131") (name "Net-(U7A-RCO)") (class "Default")
      (node (ref "JP4") (pin "1") (pinfunction "1_1") (pintype "passive"))
      (node (ref "JP4") (pin "3") (pinfunction "3_3") (pintype "passive"))
      (node (ref "JP4") (pin "5") (pinfunction "5_5") (pintype "passive"))
      (node (ref "U7") (pin "9") (pinfunction "RCO_9") (pintype "output"))
    )
    (net (code "132") (name "Net-(U8A-P=Q)") (class "Default")
      (node (ref "U8") (pin "19") (pinfunction "P=Q_19") (pintype "output"))
      (node (ref "U9") (pin "21") (pinfunction "~{CS}_21") (pintype "input"))
    )
    (net (code "133") (name "Net-(U9-BC)") (class "Default")
      (node (ref "BAT1") (pin "+") (pinfunction "+_+") (pintype "passive"))
      (node (ref "U9") (pin "24") (pinfunction "BC_24") (pintype "power_in"))
    )
    (net (code "134") (name "Net-(U9-X1)") (class "Default")
      (node (ref "U9") (pin "2") (pinfunction "X1_2") (pintype "input"))
      (node (ref "X1") (pin "1") (pinfunction "1_1") (pintype "passive"))
    )
    (net (code "135") (name "Net-(U9-X2)") (class "Default")
      (node (ref "U9") (pin "3") (pinfunction "X2_3") (pintype "input"))
      (node (ref "X1") (pin "2") (pinfunction "2_2") (pintype "passive"))
    )
    (net (code "136") (name "Net-(U9-~{RST})") (class "Default")
      (node (ref "JP2") (pin "2") (pinfunction "2_2") (pintype "passive"))
      (node (ref "U9") (pin "6") (pinfunction "~{RST}_6") (pintype "open_collector"))
    )
    (net (code "137") (name "Net-(U10A-P=Q)") (class "Default")
      (node (ref "U10") (pin "19") (pinfunction "P=Q_19") (pintype "output"))
      (node (ref "U9") (pin "23") (pinfunction "WDI_23") (pintype "input"))
    )
    (net (code "138") (name "Net-(U11A-I0)") (class "Default")
      (node (ref "U11") (pin "1") (pinfunction "I0_1") (pintype "input"))
      (node (ref "U17") (pin "15") (pinfunction "Y0_15") (pintype "output"))
      (node (ref "U19") (pin "1") (pinfunction "OC_1") (pintype "input"))
      (node (ref "U19") (pin "11") (pinfunction "C_11") (pintype "input"))
    )
    (net (code "139") (name "Net-(U11A-I1)") (class "Default")
      (node (ref "U11") (pin "2") (pinfunction "I1_2") (pintype "input"))
      (node (ref "U17") (pin "14") (pinfunction "Y1_14") (pintype "output"))
      (node (ref "U20") (pin "1") (pinfunction "OC_1") (pintype "input"))
      (node (ref "U20") (pin "11") (pinfunction "C_11") (pintype "input"))
    )
    (net (code "140") (name "Net-(U11A-I2)") (class "Default")
      (node (ref "U11") (pin "3") (pinfunction "I2_3") (pintype "input"))
      (node (ref "U17") (pin "12") (pinfunction "Y3_12") (pintype "output"))
      (node (ref "U21") (pin "1") (pinfunction "OC_1") (pintype "input"))
      (node (ref "U21") (pin "11") (pinfunction "C_11") (pintype "input"))
    )
    (net (code "141") (name "Net-(U11A-I6)") (class "Default")
      (node (ref "U11") (pin "11") (pinfunction "I6_11") (pintype "input"))
      (node (ref "U17") (pin "13") (pinfunction "Y2_13") (pintype "output"))
      (node (ref "U22") (pin "1") (pinfunction "OC_1") (pintype "input"))
      (node (ref "U22") (pin "11") (pinfunction "C_11") (pintype "input"))
    )
    (net (code "142") (name "Net-(U11A-I7)") (class "Default")
      (node (ref "U11") (pin "12") (pinfunction "I7_12") (pintype "input"))
      (node (ref "U12") (pin "13") (pinfunction "I1_13") (pintype "input"))
      (node (ref "U17") (pin "11") (pinfunction "Y4_11") (pintype "output"))
    )
    (net (code "143") (name "Net-(U11A-O)") (class "Default")
      (node (ref "U11") (pin "8") (pinfunction "O_8") (pintype "output"))
      (node (ref "U12") (pin "9") (pinfunction "I0_9") (pintype "input"))
    )
    (net (code "144") (name "Net-(U12D-O)") (class "Default")
      (node (ref "U12") (pin "11") (pinfunction "O_11") (pintype "output"))
      (node (ref "U23") (pin "11") (pinfunction "C_11") (pintype "input"))
    )
    (net (code "145") (name "Net-(U16A-P=Q)") (class "Default")
      (node (ref "U16") (pin "19") (pinfunction "P=Q_19") (pintype "output"))
      (node (ref "U17") (pin "4") (pinfunction "G2A_4") (pintype "input"))
    )
    (net (code "146") (name "Net-(U23A-8Q)") (class "Default")
      (node (ref "U23") (pin "12") (pinfunction "8Q_12") (pintype "tri_state"))
      (node (ref "U24") (pin "4") (pinfunction "/RES_4") (pintype "input"))
    )
    (net (code "147") (name "Net-(U24-CON)") (class "Default")
      (node (ref "C27") (pin "1") (pinfunction "1_1") (pintype "passive"))
      (node (ref "U24") (pin "5") (pinfunction "CON_5") (pintype "input"))
    )
    (net (code "148") (name "Net-(U24-DIS)") (class "Default")
      (node (ref "R4") (pin "1") (pinfunction "1_1") (pintype "passive"))
      (node (ref "R5") (pin "2") (pinfunction "2_2") (pintype "passive"))
      (node (ref "U24") (pin "7") (pinfunction "DIS_7") (pintype "input"))
    )
    (net (code "149") (name "Net-(U24-OUT)") (class "Default")
      (node (ref "JP3") (pin "1") (pinfunction "1_1") (pintype "passive"))
      (node (ref "U24") (pin "3") (pinfunction "OUT_3") (pintype "output"))
    )
    (net (code "150") (name "Net-(U24-TRE)") (class "Default")
      (node (ref "C28") (pin "1") (pinfunction "1_1") (pintype "passive"))
      (node (ref "R5") (pin "1") (pinfunction "1_1") (pintype "passive"))
      (node (ref "U24") (pin "2") (pinfunction "TRI_2") (pintype "input"))
      (node (ref "U24") (pin "6") (pinfunction "TRE_6") (pintype "input"))
    )
    (net (code "151") (name "unconnected-(BUSH-S-Pad16)") (class "Default")
      (node (ref "BUS") (pin "16") (pinfunction "S_16") (pintype "passive"))
    )
    (net (code "152") (name "unconnected-(BUSI-S-Pad17)") (class "Default")
      (node (ref "BUS") (pin "17") (pinfunction "S_17") (pintype "passive"))
    )
    (net (code "153") (name "unconnected-(BUSJ-S-Pad18)") (class "Default")
      (node (ref "BUS") (pin "18") (pinfunction "S_18") (pintype "passive"))
    )
    (net (code "154") (name "unconnected-(BUSK-S-Pad19)") (class "Default")
      (node (ref "BUS") (pin "19") (pinfunction "S_19") (pintype "passive"))
    )
    (net (code "155") (name "unconnected-(BUSM-S-Pad20)") (class "Default")
      (node (ref "BUS") (pin "20") (pinfunction "S_20") (pintype "passive"))
    )
    (net (code "156") (name "unconnected-(BUSN-S-Pad21)") (class "Default")
      (node (ref "BUS") (pin "21") (pinfunction "S_21") (pintype "passive"))
    )
    (net (code "157") (name "unconnected-(BUSO-S-Pad22)") (class "Default")
      (node (ref "BUS") (pin "22") (pinfunction "S_22") (pintype "passive"))
    )
    (net (code "158") (name "unconnected-(BUSY-S-Pad31)") (class "Default")
      (node (ref "BUS") (pin "31") (pinfunction "S_31") (pintype "passive"))
    )
    (net (code "159") (name "unconnected-(BUSZ-S-Pad32)") (class "Default")
      (node (ref "BUS") (pin "32") (pinfunction "S_32") (pintype "passive"))
    )
    (net (code "160") (name "unconnected-(SW1-P-Pad3)") (class "Default")
      (node (ref "SW1") (pin "3") (pinfunction "P_3") (pintype "passive"))
    )
    (net (code "161") (name "unconnected-(SW2-P-Pad3)") (class "Default")
      (node (ref "SW2") (pin "3") (pinfunction "P_3") (pintype "passive"))
    )
    (net (code "162") (name "unconnected-(SW3-P1-Pad4)") (class "Default")
      (node (ref "SW3") (pin "4") (pinfunction "P1_4") (pintype "passive"))
    )
    (net (code "163") (name "unconnected-(SW4-P-Pad3)") (class "Default")
      (node (ref "SW4") (pin "3") (pinfunction "P_3") (pintype "passive"))
    )
    (net (code "164") (name "unconnected-(U3A-B6-Pad13)") (class "Default")
      (node (ref "U3") (pin "13") (pinfunction "B6_13") (pintype "bidirectional"))
    )
    (net (code "165") (name "unconnected-(U3A-B7-Pad12)") (class "Default")
      (node (ref "U3") (pin "12") (pinfunction "B7_12") (pintype "bidirectional"))
    )
    (net (code "166") (name "unconnected-(U5-TO0-Pad7)") (class "Default")
      (node (ref "U5") (pin "7") (pinfunction "TO0_7") (pintype "output"))
    )
    (net (code "167") (name "unconnected-(U5-TO1-Pad8)") (class "Default")
      (node (ref "U5") (pin "8") (pinfunction "TO1_8") (pintype "output"))
    )
    (net (code "168") (name "unconnected-(U7A-QA-Pad15)") (class "Default")
      (node (ref "U7") (pin "15") (pinfunction "QA_15") (pintype "tri_state"))
    )
    (net (code "169") (name "unconnected-(U7A-QB-Pad1)") (class "Default")
      (node (ref "U7") (pin "1") (pinfunction "QB_1") (pintype "tri_state"))
    )
    (net (code "170") (name "unconnected-(U7A-QC-Pad2)") (class "Default")
      (node (ref "U7") (pin "2") (pinfunction "QC_2") (pintype "tri_state"))
    )
    (net (code "171") (name "unconnected-(U7A-QD-Pad3)") (class "Default")
      (node (ref "U7") (pin "3") (pinfunction "QD_3") (pintype "tri_state"))
    )
    (net (code "172") (name "unconnected-(U7A-QE-Pad4)") (class "Default")
      (node (ref "U7") (pin "4") (pinfunction "QE_4") (pintype "tri_state"))
    )
    (net (code "173") (name "unconnected-(U7A-QF-Pad5)") (class "Default")
      (node (ref "U7") (pin "5") (pinfunction "QF_5") (pintype "tri_state"))
    )
    (net (code "174") (name "unconnected-(U7A-QG-Pad6)") (class "Default")
      (node (ref "U7") (pin "6") (pinfunction "QG_6") (pintype "tri_state"))
    )
    (net (code "175") (name "unconnected-(U7A-QH-Pad7)") (class "Default")
      (node (ref "U7") (pin "7") (pinfunction "QH_7") (pintype "tri_state"))
    )
    (net (code "176") (name "unconnected-(U9-V_OUT-Pad1)") (class "Default")
      (node (ref "U9") (pin "1") (pinfunction "V_OUT_1") (pintype "bidirectional"))
    )
    (net (code "177") (name "unconnected-(U9-~{CE_OUT}-Pad25)") (class "Default")
      (node (ref "U9") (pin "25") (pinfunction "~{CE_OUT}_25") (pintype "bidirectional"))
    )
    (net (code "178") (name "unconnected-(U9-~{WDO}-Pad4)") (class "Default")
      (node (ref "U9") (pin "4") (pinfunction "~{WDO}_4") (pintype "output"))
    )
    (net (code "179") (name "unconnected-(U12A-O-Pad3)") (class "Default")
      (node (ref "U12") (pin "3") (pinfunction "O_3") (pintype "output"))
    )
    (net (code "180") (name "unconnected-(U12B-O-Pad6)") (class "Default")
      (node (ref "U12") (pin "6") (pinfunction "O_6") (pintype "output"))
    )
    (net (code "181") (name "unconnected-(U17A-Y5-Pad10)") (class "Default")
      (node (ref "U17") (pin "10") (pinfunction "Y5_10") (pintype "output"))
    )
    (net (code "182") (name "unconnected-(U17A-Y6-Pad9)") (class "Default")
      (node (ref "U17") (pin "9") (pinfunction "Y6_9") (pintype "output"))
    )
    (net (code "183") (name "unconnected-(U17A-Y7-Pad7)") (class "Default")
      (node (ref "U17") (pin "7") (pinfunction "Y7_7") (pintype "output"))
    )
    (net (code "184") (name "unconnected-(U23A-1Q-Pad19)") (class "Default")
      (node (ref "U23") (pin "19") (pinfunction "1Q_19") (pintype "tri_state"))
    )
    (net (code "185") (name "unconnected-(U23A-2Q-Pad18)") (class "Default")
      (node (ref "U23") (pin "18") (pinfunction "2Q_18") (pintype "tri_state"))
    )
    (net (code "186") (name "unconnected-(U23A-3Q-Pad17)") (class "Default")
      (node (ref "U23") (pin "17") (pinfunction "3Q_17") (pintype "tri_state"))
    )
    (net (code "187") (name "unconnected-(U23A-4Q-Pad16)") (class "Default")
      (node (ref "U23") (pin "16") (pinfunction "4Q_16") (pintype "tri_state"))
    )
    (net (code "188") (name "unconnected-(U23A-5Q-Pad15)") (class "Default")
      (node (ref "U23") (pin "15") (pinfunction "5Q_15") (pintype "tri_state"))
    )
    (net (code "189") (name "unconnected-(U23A-6Q-Pad14)") (class "Default")
      (node (ref "U23") (pin "14") (pinfunction "6Q_14") (pintype "tri_state"))
    )
    (net (code "190") (name "unconnected-(U23A-7Q-Pad13)") (class "Default")
      (node (ref "U23") (pin "13") (pinfunction "7Q_13") (pintype "tri_state"))
    )
    (net (code "191") (name "unconnected-(Y1-TS-Pad1)") (class "Default")
      (node (ref "Y1") (pin "1") (pinfunction "TS_1") (pintype "passive"))
    )
  )
)
